# bme_sensorion_board.net
KiCad netlist of a schematic drawn in Altium Designer
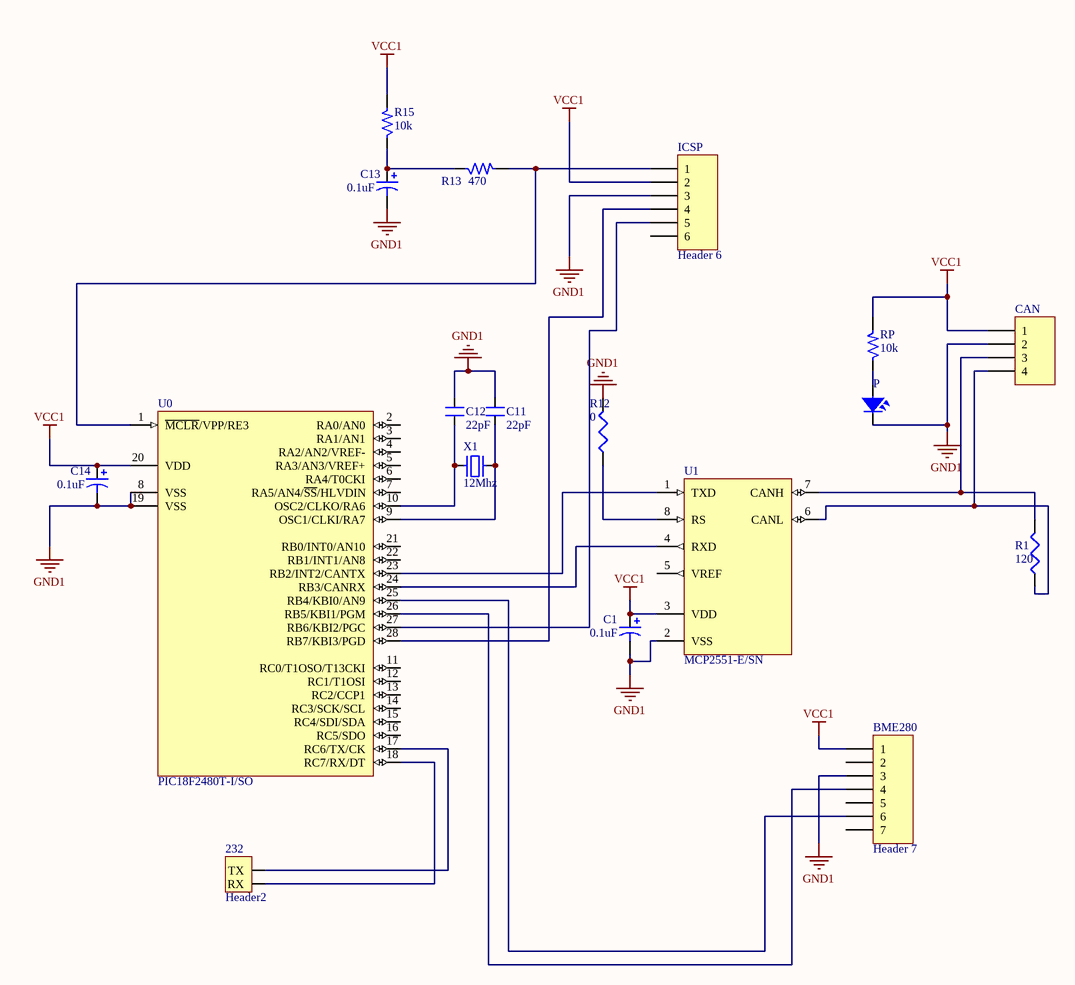
[diagram p0: bme_sensorion_board.SchDoc]

(export (version "E")
  (design (tool "Eeschema 10.0.6"))
  (components
    (comp (ref "232")
      (value "Header2")
      (footprint "HDR2")
      (description "Header IDC, 2 x 1 Pin Vertical 2.54mm Pitch (Non-Boxed, Male)")
      (fields
        (field (name "MANUFACTURER") "Würth Elektronik eiSos GmbH")
        (field (name "PARTNO") "613002143121")
        (field (name "CREATED BY") "Karrer Zheng")
      )
      (libsource (lib "LIBRARY") (part "Header2"))
    )
    (comp (ref "BME280")
      (value "Header 7")
      (footprint "HDR1X7")
      (description "Header, 7-Pin")
      (fields (field (name "PUBLISHER") "Altium Limited"))
      (libsource (lib "Miscellaneous Connectors") (part "Header 7"))
    )
    (comp (ref "C1")
      (value "0.1uF")
      (footprint "C0805")
      (description "Polarized Capacitor (Surface Mount)")
      (fields (field (name "Comment") "Cap Pol3") (field (name "PUBLISHER") "Altium Limited"))
      (libsource (lib "Miscellaneous Devices") (part "Cap Pol3"))
    )
    (comp (ref "C11")
      (value "22pF")
      (footprint "CN1")
      (description "Cremic For Xtal 1pF => 100pF")
      (libsource (lib "electronicvn-library1") (part "CN0"))
    )
    (comp (ref "C12")
      (value "22pF")
      (footprint "CN1")
      (description "Cremic For Xtal 1pF => 100pF")
      (libsource (lib "electronicvn-library1") (part "CN0"))
    )
    (comp (ref "C13")
      (value "0.1uF")
      (footprint "C0805")
      (description "Polarized Capacitor (Surface Mount)")
      (fields (field (name "Comment") "Cap Pol3") (field (name "PUBLISHER") "Altium Limited"))
      (libsource (lib "Miscellaneous Devices") (part "Cap Pol3"))
    )
    (comp (ref "C14")
      (value "0.1uF")
      (footprint "C0805")
      (description "Polarized Capacitor (Surface Mount)")
      (fields (field (name "Comment") "Cap Pol3") (field (name "PUBLISHER") "Altium Limited"))
      (libsource (lib "Miscellaneous Devices") (part "Cap Pol3"))
    )
    (comp (ref "CAN")
      (value "Header 4")
      (footprint "HDR1X4")
      (description "Header, 4-Pin")
      (fields (field (name "PUBLISHER") "Altium Limited"))
      (libsource (lib "Miscellaneous Connectors") (part "Header 4"))
    )
    (comp (ref "ICSP")
      (value "Header 6")
      (footprint "HDR1X6")
      (description "Header, 6-Pin")
      (fields (field (name "PUBLISHER") "Altium Limited"))
      (libsource (lib "Miscellaneous Connectors") (part "Header 6"))
    )
    (comp (ref "P")
      (value "LED")
      (footprint "LED-3MM-YELLOW")
      (description "LED Single colour Green and Red")
      (libsource (lib "LIBRARY") (part "LED"))
    )
    (comp (ref "R1")
      (value "120")
      (footprint "J1-0603")
      (description "Resistor")
      (fields (field (name "Comment") "Res3") (field (name "PUBLISHER") "Altium Limited"))
      (libsource (lib "Miscellaneous Devices") (part "Res3"))
    )
    (comp (ref "R12")
      (value "0")
      (footprint "J1-0603")
      (description "Resistor")
      (fields (field (name "Comment") "Res3") (field (name "PUBLISHER") "Altium Limited"))
      (libsource (lib "Miscellaneous Devices") (part "Res3"))
    )
    (comp (ref "R13")
      (value "470")
      (footprint "SM-RES-1206")
      (description "Resistor 1/4W")
      (libsource (lib "electronicvn-library1") (part "R"))
    )
    (comp (ref "R15")
      (value "10k")
      (footprint "SM-RES-1206")
      (description "Resistor 1/4W")
      (libsource (lib "electronicvn-library1") (part "R"))
    )
    (comp (ref "RP")
      (value "10k")
      (footprint "SM-RES-1206")
      (description "Resistor 1/4W")
      (libsource (lib "electronicvn-library1") (part "R"))
    )
    (comp (ref "U0")
      (value "PIC18F2480T-I/SO")
      (footprint "SOIC-SO28_L")
      (fields (field (name "PUBLISHER") "Altium Limited"))
      (libsource (lib "Microchip Microcontroller 8-Bit PIC18") (part "PIC18F2480T-I/SO"))
    )
    (comp (ref "U1")
      (value "MCP2551-E/SN")
      (footprint "SOIC-SN8_N")
      (description "High-Speed CAN Transceiver, 8-Pin SOIC, Extended Temperature")
      (fields (field (name "PUBLISHER") "Altium Limited"))
      (libsource (lib "Microchip Interface") (part "MCP2551-E/SN"))
    )
    (comp (ref "X1")
      (value "12Mhz")
      (footprint "XT2")
      (description "Crystal, 32.768 KHz, -40 to 85 degC, 3.2 x 1.5 x 0.9 mm SMD")
      (libsource (lib "LIBRARY") (part "XT2"))
    )
  )
  (nets
    (net (code "1") (name "GND1") (class "Default")
      (node (ref "BME280") (pin "3") (pinfunction "3_3") (pintype "passive"))
      (node (ref "C1") (pin "2") (pinfunction "2_2") (pintype "passive"))
      (node (ref "C11") (pin "2") (pinfunction "2_2") (pintype "passive"))
      (node (ref "C12") (pin "2") (pinfunction "2_2") (pintype "passive"))
      (node (ref "C13") (pin "2") (pinfunction "2_2") (pintype "passive"))
      (node (ref "C14") (pin "2") (pinfunction "2_2") (pintype "passive"))
      (node (ref "CAN") (pin "2") (pinfunction "2_2") (pintype "passive"))
      (node (ref "ICSP") (pin "3") (pinfunction "3_3") (pintype "passive"))
      (node (ref "P") (pin "2") (pinfunction "2_2") (pintype "passive"))
      (node (ref "R12") (pin "2") (pinfunction "2_2") (pintype "passive"))
      (node (ref "U0") (pin "19") (pinfunction "VSS_19") (pintype "power_in"))
      (node (ref "U0") (pin "8") (pinfunction "VSS_8") (pintype "power_in"))
      (node (ref "U1") (pin "2") (pinfunction "VSS_2") (pintype "power_in"))
    )
    (net (code "2") (name "Net-(232-RX)") (class "Default")
      (node (ref "232") (pin "1") (pinfunction "RX_1") (pintype "passive"))
      (node (ref "U0") (pin "18") (pinfunction "RC7/RX/DT_18") (pintype "bidirectional"))
    )
    (net (code "3") (name "Net-(232-TX)") (class "Default")
      (node (ref "232") (pin "2") (pinfunction "TX_2") (pintype "passive"))
      (node (ref "U0") (pin "17") (pinfunction "RC6/TX/CK_17") (pintype "bidirectional"))
    )
    (net (code "4") (name "Net-(C13-Pad1)") (class "Default")
      (node (ref "C13") (pin "1") (pinfunction "1_1") (pintype "passive"))
      (node (ref "R13") (pin "1") (pinfunction "1_1") (pintype "passive"))
      (node (ref "R15") (pin "1") (pinfunction "1_1") (pintype "passive"))
    )
    (net (code "5") (name "Net-(P-Pad1)") (class "Default")
      (node (ref "P") (pin "1") (pinfunction "1_1") (pintype "passive"))
      (node (ref "RP") (pin "1") (pinfunction "1_1") (pintype "passive"))
    )
    (net (code "6") (name "Net-(U0-OSC1{slash}CLKI{slash}RA7)") (class "Default")
      (node (ref "C11") (pin "1") (pinfunction "1_1") (pintype "passive"))
      (node (ref "U0") (pin "9") (pinfunction "OSC1/CLKI/RA7_9") (pintype "bidirectional"))
      (node (ref "X1") (pin "2") (pinfunction "2_2") (pintype "passive"))
    )
    (net (code "7") (name "Net-(U0-OSC2{slash}CLKO{slash}RA6)") (class "Default")
      (node (ref "C12") (pin "1") (pinfunction "1_1") (pintype "passive"))
      (node (ref "U0") (pin "10") (pinfunction "OSC2/CLKO/RA6_10") (pintype "bidirectional"))
      (node (ref "X1") (pin "1") (pinfunction "1_1") (pintype "passive"))
    )
    (net (code "8") (name "Net-(U0-RB2{slash}INT2{slash}CANTX)") (class "Default")
      (node (ref "U0") (pin "23") (pinfunction "RB2/INT2/CANTX_23") (pintype "bidirectional"))
      (node (ref "U1") (pin "1") (pinfunction "TXD_1") (pintype "input"))
    )
    (net (code "9") (name "Net-(U0-RB3{slash}CANRX)") (class "Default")
      (node (ref "U0") (pin "24") (pinfunction "RB3/CANRX_24") (pintype "bidirectional"))
      (node (ref "U1") (pin "4") (pinfunction "RXD_4") (pintype "output"))
    )
    (net (code "10") (name "Net-(U0-RB4{slash}KBI0{slash}AN9)") (class "Default")
      (node (ref "BME280") (pin "6") (pinfunction "6_6") (pintype "passive"))
      (node (ref "U0") (pin "25") (pinfunction "RB4/KBI0/AN9_25") (pintype "bidirectional"))
    )
    (net (code "11") (name "Net-(U0-RB5{slash}KBI1{slash}PGM)") (class "Default")
      (node (ref "BME280") (pin "4") (pinfunction "4_4") (pintype "passive"))
      (node (ref "U0") (pin "26") (pinfunction "RB5/KBI1/PGM_26") (pintype "bidirectional"))
    )
    (net (code "12") (name "Net-(U0-RB6{slash}KBI2{slash}PGC)") (class "Default")
      (node (ref "ICSP") (pin "5") (pinfunction "5_5") (pintype "passive"))
      (node (ref "U0") (pin "27") (pinfunction "RB6/KBI2/PGC_27") (pintype "bidirectional"))
    )
    (net (code "13") (name "Net-(U0-RB7{slash}KBI3{slash}PGD)") (class "Default")
      (node (ref "ICSP") (pin "4") (pinfunction "4_4") (pintype "passive"))
      (node (ref "U0") (pin "28") (pinfunction "RB7/KBI3/PGD_28") (pintype "bidirectional"))
    )
    (net (code "14") (name "Net-(U0-~{MCLR}{slash}VPP{slash}RE3)") (class "Default")
      (node (ref "ICSP") (pin "1") (pinfunction "1_1") (pintype "passive"))
      (node (ref "R13") (pin "2") (pinfunction "2_2") (pintype "passive"))
      (node (ref "U0") (pin "1") (pinfunction "~{MCLR}/VPP/RE3_1") (pintype "input"))
    )
    (net (code "15") (name "Net-(U1-CANH)") (class "Default")
      (node (ref "CAN") (pin "3") (pinfunction "3_3") (pintype "passive"))
      (node (ref "R1") (pin "2") (pinfunction "2_2") (pintype "passive"))
      (node (ref "U1") (pin "7") (pinfunction "CANH_7") (pintype "bidirectional"))
    )
    (net (code "16") (name "Net-(U1-CANL)") (class "Default")
      (node (ref "CAN") (pin "4") (pinfunction "4_4") (pintype "passive"))
      (node (ref "R1") (pin "1") (pinfunction "1_1") (pintype "passive"))
      (node (ref "U1") (pin "6") (pinfunction "CANL_6") (pintype "bidirectional"))
    )
    (net (code "17") (name "Net-(U1-RS)") (class "Default")
      (node (ref "R12") (pin "1") (pinfunction "1_1") (pintype "passive"))
      (node (ref "U1") (pin "8") (pinfunction "RS_8") (pintype "input"))
    )
    (net (code "18") (name "VCC1") (class "Default")
      (node (ref "BME280") (pin "1") (pinfunction "1_1") (pintype "passive"))
      (node (ref "C1") (pin "1") (pinfunction "1_1") (pintype "passive"))
      (node (ref "C14") (pin "1") (pinfunction "1_1") (pintype "passive"))
      (node (ref "CAN") (pin "1") (pinfunction "1_1") (pintype "passive"))
      (node (ref "ICSP") (pin "2") (pinfunction "2_2") (pintype "passive"))
      (node (ref "R15") (pin "2") (pinfunction "2_2") (pintype "passive"))
      (node (ref "RP") (pin "2") (pinfunction "2_2") (pintype "passive"))
      (node (ref "U0") (pin "20") (pinfunction "VDD_20") (pintype "power_in"))
      (node (ref "U1") (pin "3") (pinfunction "VDD_3") (pintype "power_in"))
    )
    (net (code "19") (name "unconnected-(BME280-Pad2)") (class "Default")
      (node (ref "BME280") (pin "2") (pinfunction "2_2") (pintype "passive"))
    )
    (net (code "20") (name "unconnected-(BME280-Pad5)") (class "Default")
      (node (ref "BME280") (pin "5") (pinfunction "5_5") (pintype "passive"))
    )
    (net (code "21") (name "unconnected-(BME280-Pad7)") (class "Default")
      (node (ref "BME280") (pin "7") (pinfunction "7_7") (pintype "passive"))
    )
    (net (code "22") (name "unconnected-(ICSP-Pad6)") (class "Default")
      (node (ref "ICSP") (pin "6") (pinfunction "6_6") (pintype "passive"))
    )
    (net (code "23") (name "unconnected-(U0-RA0{slash}AN0-Pad2)") (class "Default")
      (node (ref "U0") (pin "2") (pinfunction "RA0/AN0_2") (pintype "bidirectional"))
    )
    (net (code "24") (name "unconnected-(U0-RA1{slash}AN1-Pad3)") (class "Default")
      (node (ref "U0") (pin "3") (pinfunction "RA1/AN1_3") (pintype "bidirectional"))
    )
    (net (code "25") (name "unconnected-(U0-RA2{slash}AN2{slash}VREF--Pad4)") (class "Default")
      (node (ref "U0") (pin "4") (pinfunction "RA2/AN2/VREF-_4") (pintype "bidirectional"))
    )
    (net (code "26") (name "unconnected-(U0-RA3{slash}AN3{slash}VREF+-Pad5)") (class "Default")
      (node (ref "U0") (pin "5") (pinfunction "RA3/AN3/VREF+_5") (pintype "bidirectional"))
    )
    (net (code "27") (name "unconnected-(U0-RA4{slash}T0CKI-Pad6)") (class "Default")
      (node (ref "U0") (pin "6") (pinfunction "RA4/T0CKI_6") (pintype "bidirectional"))
    )
    (net (code "28") (name "unconnected-(U0-RA5{slash}AN4{slash}~{SS}{slash}HLVDIN-Pad7)") (class "Default")
      (node (ref "U0") (pin "7") (pinfunction "RA5/AN4/~{SS}/HLVDIN_7") (pintype "bidirectional"))
    )
    (net (code "29") (name "unconnected-(U0-RB0{slash}INT0{slash}AN10-Pad21)") (class "Default")
      (node (ref "U0") (pin "21") (pinfunction "RB0/INT0/AN10_21") (pintype "bidirectional"))
    )
    (net (code "30") (name "unconnected-(U0-RB1{slash}INT1{slash}AN8-Pad22)") (class "Default")
      (node (ref "U0") (pin "22") (pinfunction "RB1/INT1/AN8_22") (pintype "bidirectional"))
    )
    (net (code "31") (name "unconnected-(U0-RC0{slash}T1OSO{slash}T13CKI-Pad11)") (class "Default")
      (node (ref "U0") (pin "11") (pinfunction "RC0/T1OSO/T13CKI_11") (pintype "bidirectional"))
    )
    (net (code "32") (name "unconnected-(U0-RC1{slash}T1OSI-Pad12)") (class "Default")
      (node (ref "U0") (pin "12") (pinfunction "RC1/T1OSI_12") (pintype "bidirectional"))
    )
    (net (code "33") (name "unconnected-(U0-RC2{slash}CCP1-Pad13)") (class "Default")
      (node (ref "U0") (pin "13") (pinfunction "RC2/CCP1_13") (pintype "bidirectional"))
    )
    (net (code "34") (name "unconnected-(U0-RC3{slash}SCK{slash}SCL-Pad14)") (class "Default")
      (node (ref "U0") (pin "14") (pinfunction "RC3/SCK/SCL_14") (pintype "bidirectional"))
    )
    (net (code "35") (name "unconnected-(U0-RC4{slash}SDI{slash}SDA-Pad15)") (class "Default")
      (node (ref "U0") (pin "15") (pinfunction "RC4/SDI/SDA_15") (pintype "bidirectional"))
    )
    (net (code "36") (name "unconnected-(U0-RC5{slash}SDO-Pad16)") (class "Default")
      (node (ref "U0") (pin "16") (pinfunction "RC5/SDO_16") (pintype "bidirectional"))
    )
    (net (code "37") (name "unconnected-(U1-VREF-Pad5)") (class "Default")
      (node (ref "U1") (pin "5") (pinfunction "VREF_5") (pintype "output"))
    )
  )
)
